# tb_target.net
KiCad netlist of a schematic drawn in EAGLE
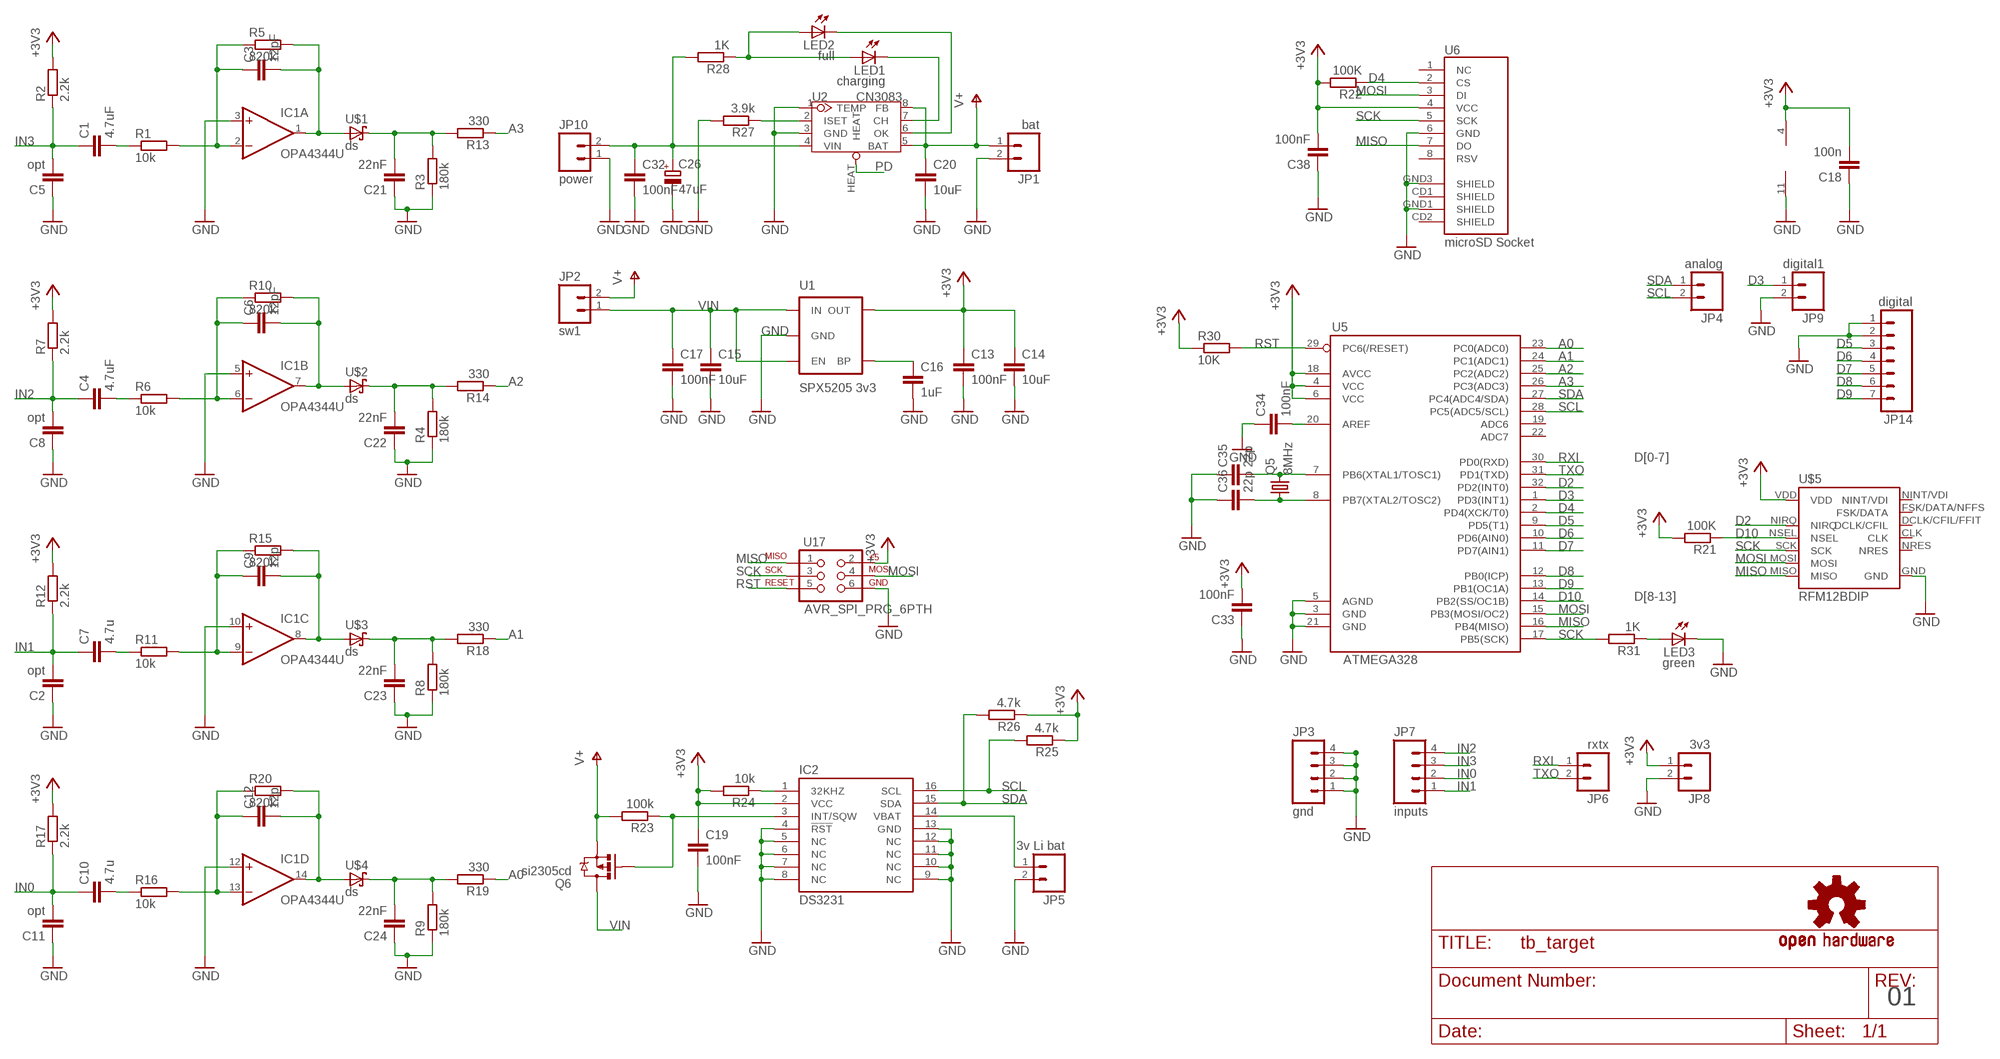
[diagram p0: schematic, sheet 1]

(export (version "E")
  (design (tool "Eeschema 10.0.6"))
  (components
    (comp (ref "C1")
      (value "4.7uF")
      (footprint "eagle-import:C0805")
      (libsource (lib "eagle-import") (part "resistor_C-EUC0805"))
    )
    (comp (ref "C2")
      (value "opt")
      (footprint "eagle-import:C0805")
      (libsource (lib "eagle-import") (part "resistor_C-EUC0805"))
    )
    (comp (ref "C3")
      (value "12pF")
      (footprint "eagle-import:C0805")
      (libsource (lib "eagle-import") (part "resistor_C-EUC0805"))
    )
    (comp (ref "C4")
      (value "4.7uF")
      (footprint "eagle-import:C0805")
      (libsource (lib "eagle-import") (part "resistor_C-EUC0805"))
    )
    (comp (ref "C5")
      (value "opt")
      (footprint "eagle-import:C0805")
      (libsource (lib "eagle-import") (part "resistor_C-EUC0805"))
    )
    (comp (ref "C6")
      (value "12pF")
      (footprint "eagle-import:C0805")
      (libsource (lib "eagle-import") (part "resistor_C-EUC0805"))
    )
    (comp (ref "C7")
      (value "4.7u")
      (footprint "eagle-import:C0805")
      (libsource (lib "eagle-import") (part "resistor_C-EUC0805"))
    )
    (comp (ref "C8")
      (value "opt")
      (footprint "eagle-import:C0805")
      (libsource (lib "eagle-import") (part "resistor_C-EUC0805"))
    )
    (comp (ref "C9")
      (value "12p")
      (footprint "eagle-import:C0805")
      (libsource (lib "eagle-import") (part "resistor_C-EUC0805"))
    )
    (comp (ref "C10")
      (value "4.7u")
      (footprint "eagle-import:C0805")
      (libsource (lib "eagle-import") (part "resistor_C-EUC0805"))
    )
    (comp (ref "C11")
      (value "opt")
      (footprint "eagle-import:C0805")
      (libsource (lib "eagle-import") (part "resistor_C-EUC0805"))
    )
    (comp (ref "C12")
      (value "12p")
      (footprint "eagle-import:C0805")
      (libsource (lib "eagle-import") (part "resistor_C-EUC0805"))
    )
    (comp (ref "C13")
      (value "100nF")
      (footprint "eagle-import:C0805")
      (libsource (lib "eagle-import") (part "C-EUC0805"))
    )
    (comp (ref "C14")
      (value "10uF")
      (footprint "eagle-import:C1206")
      (libsource (lib "eagle-import") (part "C-EUC1206"))
    )
    (comp (ref "C15")
      (value "10uF")
      (footprint "eagle-import:C1206")
      (libsource (lib "eagle-import") (part "C-EUC1206"))
    )
    (comp (ref "C16")
      (value "1uF")
      (footprint "eagle-import:C0805")
      (libsource (lib "eagle-import") (part "C-EUC0805"))
    )
    (comp (ref "C17")
      (value "100nF")
      (footprint "eagle-import:C0805")
      (libsource (lib "eagle-import") (part "C-EUC0805"))
    )
    (comp (ref "C18")
      (value "100n")
      (footprint "eagle-import:C0805")
      (libsource (lib "eagle-import") (part "resistor_C-EUC0805"))
    )
    (comp (ref "C19")
      (value "100nF")
      (footprint "eagle-import:C0805")
      (libsource (lib "eagle-import") (part "C-EUC0805"))
    )
    (comp (ref "C20")
      (value "10uF")
      (footprint "eagle-import:C1206")
      (libsource (lib "eagle-import") (part "C-EUC1206"))
    )
    (comp (ref "C21")
      (value "22nF")
      (footprint "eagle-import:C0805")
      (libsource (lib "eagle-import") (part "resistor_C-EUC0805"))
    )
    (comp (ref "C22")
      (value "22nF")
      (footprint "eagle-import:C0805")
      (libsource (lib "eagle-import") (part "resistor_C-EUC0805"))
    )
    (comp (ref "C23")
      (value "22nF")
      (footprint "eagle-import:C0805")
      (libsource (lib "eagle-import") (part "resistor_C-EUC0805"))
    )
    (comp (ref "C24")
      (value "22nF")
      (footprint "eagle-import:C0805")
      (libsource (lib "eagle-import") (part "resistor_C-EUC0805"))
    )
    (comp (ref "C26")
      (value "47uF")
      (footprint "eagle-import:CT7343")
      (libsource (lib "eagle-import") (part "CPOL-EUCT7343"))
    )
    (comp (ref "C32")
      (value "100nF")
      (footprint "eagle-import:C0805")
      (libsource (lib "eagle-import") (part "C-EUC0805"))
    )
    (comp (ref "C33")
      (value "100nF")
      (footprint "eagle-import:C0805")
      (libsource (lib "eagle-import") (part "C-EUC0805"))
    )
    (comp (ref "C34")
      (value "100nF")
      (footprint "eagle-import:C0805")
      (libsource (lib "eagle-import") (part "C-EUC0805"))
    )
    (comp (ref "C35")
      (value "22p")
      (footprint "eagle-import:C0805")
      (libsource (lib "eagle-import") (part "C-EUC0805"))
    )
    (comp (ref "C36")
      (value "22p")
      (footprint "eagle-import:C0805")
      (libsource (lib "eagle-import") (part "C-EUC0805"))
    )
    (comp (ref "C38")
      (value "100nF")
      (footprint "eagle-import:C0805")
      (libsource (lib "eagle-import") (part "C-EUC0805"))
    )
    (comp (ref "IC1")
      (value "OPA4344U")
      (footprint "eagle-import:SO14")
      (libsource (lib "eagle-import") (part "OPA4U344"))
    )
    (comp (ref "IC2")
      (value "DS3231")
      (footprint "eagle-import:SO-16")
      (libsource (lib "eagle-import") (part "DS3231"))
    )
    (comp (ref "JP1")
      (value "bat")
      (footprint "eagle-import:1X02")
      (libsource (lib "eagle-import") (part "M02PTH"))
    )
    (comp (ref "JP2")
      (value "sw1")
      (footprint "eagle-import:1X02")
      (libsource (lib "eagle-import") (part "M02PTH"))
    )
    (comp (ref "JP3")
      (value "gnd")
      (footprint "eagle-import:1X04")
      (libsource (lib "eagle-import") (part "M04PTH"))
    )
    (comp (ref "JP4")
      (value "analog")
      (footprint "eagle-import:1X02")
      (libsource (lib "eagle-import") (part "M02PTH"))
    )
    (comp (ref "JP5")
      (value "3v Li bat")
      (footprint "eagle-import:1X02")
      (libsource (lib "eagle-import") (part "M02PTH"))
    )
    (comp (ref "JP6")
      (value "rxtx")
      (footprint "eagle-import:1X02")
      (libsource (lib "eagle-import") (part "M02PTH"))
    )
    (comp (ref "JP7")
      (value "inputs")
      (footprint "eagle-import:1X04")
      (libsource (lib "eagle-import") (part "M04PTH"))
    )
    (comp (ref "JP8")
      (value "3v3")
      (footprint "eagle-import:1X02")
      (libsource (lib "eagle-import") (part "M02PTH"))
    )
    (comp (ref "JP9")
      (value "digital1")
      (footprint "eagle-import:1X02")
      (libsource (lib "eagle-import") (part "M02PTH"))
    )
    (comp (ref "JP10")
      (value "power")
      (footprint "eagle-import:1X02")
      (libsource (lib "eagle-import") (part "M02PTH"))
    )
    (comp (ref "JP14")
      (value "digital")
      (footprint "eagle-import:1X07")
      (libsource (lib "eagle-import") (part "M07"))
    )
    (comp (ref "LED1")
      (value "charging")
      (footprint "eagle-import:CHIP-LED0805")
      (libsource (lib "eagle-import") (part "LEDCHIP-LED0805"))
    )
    (comp (ref "LED2")
      (value "full")
      (footprint "eagle-import:CHIP-LED0805")
      (libsource (lib "eagle-import") (part "LEDCHIP-LED0805"))
    )
    (comp (ref "LED3")
      (value "green")
      (footprint "eagle-import:CHIP-LED0805")
      (libsource (lib "eagle-import") (part "LEDCHIP-LED0805"))
    )
    (comp (ref "Q5")
      (value "8MHz")
      (footprint "eagle-import:CRYSTAL_5X3.2")
      (libsource (lib "eagle-import") (part "CRYTAL"))
    )
    (comp (ref "Q6")
      (value "si2305cd")
      (footprint "eagle-import:SOT23-3_POWER")
      (libsource (lib "eagle-import") (part "MOSFET-PCHANNELSMD_POWER"))
    )
    (comp (ref "R1")
      (value "10k")
      (footprint "eagle-import:R0805W")
      (libsource (lib "eagle-import") (part "resistor_R-EU_R0805W"))
    )
    (comp (ref "R2")
      (value "2.2k")
      (footprint "eagle-import:R0805W")
      (libsource (lib "eagle-import") (part "resistor_R-EU_R0805W"))
    )
    (comp (ref "R3")
      (value "180k")
      (footprint "eagle-import:R0805W")
      (libsource (lib "eagle-import") (part "resistor_R-EU_R0805W"))
    )
    (comp (ref "R4")
      (value "180k")
      (footprint "eagle-import:R0805W")
      (libsource (lib "eagle-import") (part "resistor_R-EU_R0805W"))
    )
    (comp (ref "R5")
      (value "820k")
      (footprint "eagle-import:R0805W")
      (libsource (lib "eagle-import") (part "resistor_R-EU_R0805W"))
    )
    (comp (ref "R6")
      (value "10k")
      (footprint "eagle-import:R0805W")
      (libsource (lib "eagle-import") (part "resistor_R-EU_R0805W"))
    )
    (comp (ref "R7")
      (value "2.2k")
      (footprint "eagle-import:R0805W")
      (libsource (lib "eagle-import") (part "resistor_R-EU_R0805W"))
    )
    (comp (ref "R8")
      (value "180k")
      (footprint "eagle-import:R0805W")
      (libsource (lib "eagle-import") (part "resistor_R-EU_R0805W"))
    )
    (comp (ref "R9")
      (value "180k")
      (footprint "eagle-import:R0805W")
      (libsource (lib "eagle-import") (part "resistor_R-EU_R0805W"))
    )
    (comp (ref "R10")
      (value "820k")
      (footprint "eagle-import:R0805W")
      (libsource (lib "eagle-import") (part "resistor_R-EU_R0805W"))
    )
    (comp (ref "R11")
      (value "10k")
      (footprint "eagle-import:R0805W")
      (libsource (lib "eagle-import") (part "resistor_R-EU_R0805W"))
    )
    (comp (ref "R12")
      (value "2.2k")
      (footprint "eagle-import:R0805W")
      (libsource (lib "eagle-import") (part "resistor_R-EU_R0805W"))
    )
    (comp (ref "R13")
      (value "330")
      (footprint "eagle-import:R0805W")
      (libsource (lib "eagle-import") (part "resistor_R-EU_R0805W"))
    )
    (comp (ref "R14")
      (value "330")
      (footprint "eagle-import:R0805W")
      (libsource (lib "eagle-import") (part "resistor_R-EU_R0805W"))
    )
    (comp (ref "R15")
      (value "820k")
      (footprint "eagle-import:R0805W")
      (libsource (lib "eagle-import") (part "resistor_R-EU_R0805W"))
    )
    (comp (ref "R16")
      (value "10k")
      (footprint "eagle-import:R0805W")
      (libsource (lib "eagle-import") (part "resistor_R-EU_R0805W"))
    )
    (comp (ref "R17")
      (value "2.2k")
      (footprint "eagle-import:R0805W")
      (libsource (lib "eagle-import") (part "resistor_R-EU_R0805W"))
    )
    (comp (ref "R18")
      (value "330")
      (footprint "eagle-import:R0805W")
      (libsource (lib "eagle-import") (part "resistor_R-EU_R0805W"))
    )
    (comp (ref "R19")
      (value "330")
      (footprint "eagle-import:R0805W")
      (libsource (lib "eagle-import") (part "resistor_R-EU_R0805W"))
    )
    (comp (ref "R20")
      (value "820k")
      (footprint "eagle-import:R0805W")
      (libsource (lib "eagle-import") (part "resistor_R-EU_R0805W"))
    )
    (comp (ref "R21")
      (value "100K")
      (footprint "eagle-import:R0805W")
      (libsource (lib "eagle-import") (part "R-EU_R0805W"))
    )
    (comp (ref "R22")
      (value "100K")
      (footprint "eagle-import:R0805W")
      (libsource (lib "eagle-import") (part "R-EU_R0805W"))
    )
    (comp (ref "R23")
      (value "100k")
      (footprint "eagle-import:R0805W")
      (libsource (lib "eagle-import") (part "R-EU_R0805W"))
    )
    (comp (ref "R24")
      (value "10k")
      (footprint "eagle-import:R0805W")
      (libsource (lib "eagle-import") (part "R-EU_R0805W"))
    )
    (comp (ref "R25")
      (value "4.7k")
      (footprint "eagle-import:R0805W")
      (libsource (lib "eagle-import") (part "R-EU_R0805W"))
    )
    (comp (ref "R26")
      (value "4.7k")
      (footprint "eagle-import:R0805W")
      (libsource (lib "eagle-import") (part "R-EU_R0805W"))
    )
    (comp (ref "R27")
      (value "3.9k")
      (footprint "eagle-import:R0805W")
      (libsource (lib "eagle-import") (part "R-EU_R0805W"))
    )
    (comp (ref "R28")
      (value "1K")
      (footprint "eagle-import:R0805W")
      (libsource (lib "eagle-import") (part "R-EU_R0805W"))
    )
    (comp (ref "R30")
      (value "10K")
      (footprint "eagle-import:R0805W")
      (libsource (lib "eagle-import") (part "R-EU_R0805W"))
    )
    (comp (ref "R31")
      (value "1K")
      (footprint "eagle-import:R0805W")
      (libsource (lib "eagle-import") (part "R-EU_R0805W"))
    )
    (comp (ref "U$1")
      (value "ds")
      (footprint "eagle-import:SOD80")
      (libsource (lib "eagle-import") (part "DIODE-SCHOTTKYMINIMELF"))
    )
    (comp (ref "U$2")
      (value "ds")
      (footprint "eagle-import:SOD80")
      (libsource (lib "eagle-import") (part "DIODE-SCHOTTKYMINIMELF"))
    )
    (comp (ref "U$3")
      (value "ds")
      (footprint "eagle-import:SOD80")
      (libsource (lib "eagle-import") (part "DIODE-SCHOTTKYMINIMELF"))
    )
    (comp (ref "U$4")
      (value "ds")
      (footprint "eagle-import:SOD80")
      (libsource (lib "eagle-import") (part "DIODE-SCHOTTKYMINIMELF"))
    )
    (comp (ref "U$5")
      (value "RFM12BDIP")
      (footprint "eagle-import:RFM12B_DIP")
      (libsource (lib "eagle-import") (part "RFM12BDIP"))
    )
    (comp (ref "U$7")
      (value "OSHW-LOGOM")
      (footprint "eagle-import:OSHW-LOGO-M")
      (libsource (lib "eagle-import") (part "OSHW-LOGOM"))
    )
    (comp (ref "U1")
      (value "SPX5205 3v3")
      (footprint "eagle-import:SOT23-5")
      (libsource (lib "eagle-import") (part "V_REG_LDOSMD"))
    )
    (comp (ref "U2")
      (value "CN3083")
      (footprint "eagle-import:SOP8-W_-HEAT")
      (libsource (lib "eagle-import") (part "CN3083"))
    )
    (comp (ref "U5")
      (value "ATMEGA328")
      (footprint "eagle-import:TQFP32-08")
      (libsource (lib "eagle-import") (part "ATMEGA168"))
    )
    (comp (ref "U6")
      (value "microSD Socket")
      (footprint "eagle-import:MICRO-SD-SOCKET-PP")
      (libsource (lib "eagle-import") (part "USD-SOCKETNEW"))
    )
    (comp (ref "U17")
      (value "AVR_SPI_PRG_6PTH")
      (footprint "eagle-import:2X3")
      (libsource (lib "eagle-import") (part "AVR_SPI_PRG_6PTH"))
    )
  )
  (nets
    (net (code "1") (name "+3V3") (class "Default")
      (node (ref "C13") (pin "1") (pinfunction "1_1") (pintype "passive"))
      (node (ref "C14") (pin "1") (pinfunction "1_1") (pintype "passive"))
      (node (ref "C18") (pin "2") (pinfunction "2_2") (pintype "passive"))
      (node (ref "C19") (pin "1") (pinfunction "1_1") (pintype "passive"))
      (node (ref "C33") (pin "2") (pinfunction "2_2") (pintype "passive"))
      (node (ref "C38") (pin "2") (pinfunction "2_2") (pintype "passive"))
      (node (ref "IC1") (pin "4") (pinfunction "V+_4") (pintype "power_in"))
      (node (ref "IC2") (pin "2") (pinfunction "VCC_2") (pintype "power_in"))
      (node (ref "JP8") (pin "1") (pinfunction "1_1") (pintype "passive"))
      (node (ref "R12") (pin "2") (pinfunction "2_2") (pintype "passive"))
      (node (ref "R17") (pin "2") (pinfunction "2_2") (pintype "passive"))
      (node (ref "R2") (pin "2") (pinfunction "2_2") (pintype "passive"))
      (node (ref "R21") (pin "2") (pinfunction "2_2") (pintype "passive"))
      (node (ref "R22") (pin "2") (pinfunction "2_2") (pintype "passive"))
      (node (ref "R24") (pin "2") (pinfunction "2_2") (pintype "passive"))
      (node (ref "R25") (pin "1") (pinfunction "1_1") (pintype "passive"))
      (node (ref "R26") (pin "1") (pinfunction "1_1") (pintype "passive"))
      (node (ref "R30") (pin "1") (pinfunction "1_1") (pintype "passive"))
      (node (ref "R7") (pin "2") (pinfunction "2_2") (pintype "passive"))
      (node (ref "U$5") (pin "VDD") (pinfunction "VDD_VDD") (pintype "power_in"))
      (node (ref "U1") (pin "5") (pinfunction "OUT_5") (pintype "passive"))
      (node (ref "U17") (pin "2") (pinfunction "2_2") (pintype "passive"))
      (node (ref "U5") (pin "18") (pinfunction "AVCC_18") (pintype "bidirectional"))
      (node (ref "U5") (pin "4") (pinfunction "VCC_4") (pintype "bidirectional"))
      (node (ref "U5") (pin "6") (pinfunction "VCC_6") (pintype "bidirectional"))
      (node (ref "U6") (pin "4") (pinfunction "VCC_4") (pintype "bidirectional"))
    )
    (net (code "2") (name "/A0") (class "Default")
      (node (ref "R19") (pin "1") (pinfunction "1_1") (pintype "passive"))
      (node (ref "U5") (pin "23") (pinfunction "PC0(ADC0)_23") (pintype "bidirectional"))
    )
    (net (code "3") (name "/A1") (class "Default")
      (node (ref "R18") (pin "1") (pinfunction "1_1") (pintype "passive"))
      (node (ref "U5") (pin "24") (pinfunction "PC1(ADC1)_24") (pintype "bidirectional"))
    )
    (net (code "4") (name "/A2") (class "Default")
      (node (ref "R14") (pin "1") (pinfunction "1_1") (pintype "passive"))
      (node (ref "U5") (pin "25") (pinfunction "PC2(ADC2)_25") (pintype "bidirectional"))
    )
    (net (code "5") (name "/A3") (class "Default")
      (node (ref "R13") (pin "1") (pinfunction "1_1") (pintype "passive"))
      (node (ref "U5") (pin "26") (pinfunction "PC3(ADC3)_26") (pintype "bidirectional"))
    )
    (net (code "6") (name "/D2") (class "Default")
      (node (ref "U$5") (pin "NIRQ") (pinfunction "NIRQ_NIRQ") (pintype "output"))
      (node (ref "U5") (pin "32") (pinfunction "PD2(INT0)_32") (pintype "bidirectional"))
    )
    (net (code "7") (name "/D3") (class "Default")
      (node (ref "JP9") (pin "1") (pinfunction "1_1") (pintype "passive"))
      (node (ref "U5") (pin "1") (pinfunction "PD3(INT1)_1") (pintype "bidirectional"))
    )
    (net (code "8") (name "/D4") (class "Default")
      (node (ref "R22") (pin "1") (pinfunction "1_1") (pintype "passive"))
      (node (ref "U5") (pin "2") (pinfunction "PD4(XCK/T0)_2") (pintype "bidirectional"))
      (node (ref "U6") (pin "2") (pinfunction "CS_2") (pintype "bidirectional"))
    )
    (net (code "9") (name "/D5") (class "Default")
      (node (ref "JP14") (pin "3") (pinfunction "3_3") (pintype "passive"))
      (node (ref "U5") (pin "9") (pinfunction "PD5(T1)_9") (pintype "bidirectional"))
    )
    (net (code "10") (name "/D6") (class "Default")
      (node (ref "JP14") (pin "4") (pinfunction "4_4") (pintype "passive"))
      (node (ref "U5") (pin "10") (pinfunction "PD6(AIN0)_10") (pintype "bidirectional"))
    )
    (net (code "11") (name "/D7") (class "Default")
      (node (ref "JP14") (pin "5") (pinfunction "5_5") (pintype "passive"))
      (node (ref "U5") (pin "11") (pinfunction "PD7(AIN1)_11") (pintype "bidirectional"))
    )
    (net (code "12") (name "/D8") (class "Default")
      (node (ref "JP14") (pin "6") (pinfunction "6_6") (pintype "passive"))
      (node (ref "U5") (pin "12") (pinfunction "PB0(ICP)_12") (pintype "bidirectional"))
    )
    (net (code "13") (name "/D9") (class "Default")
      (node (ref "JP14") (pin "7") (pinfunction "7_7") (pintype "passive"))
      (node (ref "U5") (pin "13") (pinfunction "PB1(OC1A)_13") (pintype "bidirectional"))
    )
    (net (code "14") (name "/D10") (class "Default")
      (node (ref "R21") (pin "1") (pinfunction "1_1") (pintype "passive"))
      (node (ref "U$5") (pin "NSEL") (pinfunction "NSEL_NSEL") (pintype "input"))
      (node (ref "U5") (pin "14") (pinfunction "PB2(SS/OC1B)_14") (pintype "bidirectional"))
    )
    (net (code "15") (name "/IN0") (class "Default")
      (node (ref "C10") (pin "1") (pinfunction "1_1") (pintype "passive"))
      (node (ref "C11") (pin "2") (pinfunction "2_2") (pintype "passive"))
      (node (ref "JP7") (pin "2") (pinfunction "2_2") (pintype "passive"))
      (node (ref "R17") (pin "1") (pinfunction "1_1") (pintype "passive"))
    )
    (net (code "16") (name "/IN1") (class "Default")
      (node (ref "C2") (pin "2") (pinfunction "2_2") (pintype "passive"))
      (node (ref "C7") (pin "1") (pinfunction "1_1") (pintype "passive"))
      (node (ref "JP7") (pin "1") (pinfunction "1_1") (pintype "passive"))
      (node (ref "R12") (pin "1") (pinfunction "1_1") (pintype "passive"))
    )
    (net (code "17") (name "/IN2") (class "Default")
      (node (ref "C4") (pin "1") (pinfunction "1_1") (pintype "passive"))
      (node (ref "C8") (pin "2") (pinfunction "2_2") (pintype "passive"))
      (node (ref "JP7") (pin "4") (pinfunction "4_4") (pintype "passive"))
      (node (ref "R7") (pin "1") (pinfunction "1_1") (pintype "passive"))
    )
    (net (code "18") (name "/IN3") (class "Default")
      (node (ref "C1") (pin "1") (pinfunction "1_1") (pintype "passive"))
      (node (ref "C5") (pin "2") (pinfunction "2_2") (pintype "passive"))
      (node (ref "JP7") (pin "3") (pinfunction "3_3") (pintype "passive"))
      (node (ref "R2") (pin "1") (pinfunction "1_1") (pintype "passive"))
    )
    (net (code "19") (name "/MISO") (class "Default")
      (node (ref "U$5") (pin "MISO") (pinfunction "MISO_MISO") (pintype "output"))
      (node (ref "U17") (pin "1") (pinfunction "1_1") (pintype "passive"))
      (node (ref "U5") (pin "16") (pinfunction "PB4(MISO)_16") (pintype "bidirectional"))
      (node (ref "U6") (pin "7") (pinfunction "DO_7") (pintype "bidirectional"))
    )
    (net (code "20") (name "/MOSI") (class "Default")
      (node (ref "U$5") (pin "MOSI") (pinfunction "MOSI_MOSI") (pintype "input"))
      (node (ref "U17") (pin "4") (pinfunction "4_4") (pintype "passive"))
      (node (ref "U5") (pin "15") (pinfunction "PB3(MOSI/OC2)_15") (pintype "bidirectional"))
      (node (ref "U6") (pin "3") (pinfunction "DI_3") (pintype "bidirectional"))
    )
    (net (code "21") (name "/PD") (class "Default")
      (node (ref "U2") (pin "HEAT") (pinfunction "HEAT_HEAT") (pintype "bidirectional"))
    )
    (net (code "22") (name "/RST") (class "Default")
      (node (ref "R30") (pin "2") (pinfunction "2_2") (pintype "passive"))
      (node (ref "U17") (pin "5") (pinfunction "5_5") (pintype "passive"))
      (node (ref "U5") (pin "29") (pinfunction "PC6(/RESET)_29") (pintype "bidirectional"))
    )
    (net (code "23") (name "/RXI") (class "Default")
      (node (ref "JP6") (pin "1") (pinfunction "1_1") (pintype "passive"))
      (node (ref "U5") (pin "30") (pinfunction "PD0(RXD)_30") (pintype "bidirectional"))
    )
    (net (code "24") (name "/SCK") (class "Default")
      (node (ref "R31") (pin "2") (pinfunction "2_2") (pintype "passive"))
      (node (ref "U$5") (pin "SCK") (pinfunction "SCK_SCK") (pintype "input"))
      (node (ref "U17") (pin "3") (pinfunction "3_3") (pintype "passive"))
      (node (ref "U5") (pin "17") (pinfunction "PB5(SCK)_17") (pintype "bidirectional"))
      (node (ref "U6") (pin "5") (pinfunction "SCK_5") (pintype "bidirectional"))
    )
    (net (code "25") (name "/SCL") (class "Default")
      (node (ref "IC2") (pin "16") (pinfunction "SCL_16") (pintype "bidirectional"))
      (node (ref "JP4") (pin "2") (pinfunction "2_2") (pintype "passive"))
      (node (ref "R25") (pin "2") (pinfunction "2_2") (pintype "passive"))
      (node (ref "U5") (pin "28") (pinfunction "PC5(ADC5/SCL)_28") (pintype "bidirectional"))
    )
    (net (code "26") (name "/SDA") (class "Default")
      (node (ref "IC2") (pin "15") (pinfunction "SDA_15") (pintype "bidirectional"))
      (node (ref "JP4") (pin "1") (pinfunction "1_1") (pintype "passive"))
      (node (ref "R26") (pin "2") (pinfunction "2_2") (pintype "passive"))
      (node (ref "U5") (pin "27") (pinfunction "PC4(ADC4/SDA)_27") (pintype "bidirectional"))
    )
    (net (code "27") (name "/TXO") (class "Default")
      (node (ref "JP6") (pin "2") (pinfunction "2_2") (pintype "passive"))
      (node (ref "U5") (pin "31") (pinfunction "PD1(TXD)_31") (pintype "bidirectional"))
    )
    (net (code "28") (name "/VIN") (class "Default")
      (node (ref "C15") (pin "1") (pinfunction "1_1") (pintype "passive"))
      (node (ref "C17") (pin "1") (pinfunction "1_1") (pintype "passive"))
      (node (ref "JP2") (pin "1") (pinfunction "1_1") (pintype "passive"))
      (node (ref "Q6") (pin "3") (pinfunction "D_3") (pintype "passive"))
      (node (ref "U1") (pin "1") (pinfunction "IN_1") (pintype "input"))
      (node (ref "U1") (pin "3") (pinfunction "EN_3") (pintype "input"))
    )
    (net (code "29") (name "GND") (class "Default")
      (node (ref "C11") (pin "1") (pinfunction "1_1") (pintype "passive"))
      (node (ref "C13") (pin "2") (pinfunction "2_2") (pintype "passive"))
      (node (ref "C14") (pin "2") (pinfunction "2_2") (pintype "passive"))
      (node (ref "C15") (pin "2") (pinfunction "2_2") (pintype "passive"))
      (node (ref "C16") (pin "2") (pinfunction "2_2") (pintype "passive"))
      (node (ref "C17") (pin "2") (pinfunction "2_2") (pintype "passive"))
      (node (ref "C18") (pin "1") (pinfunction "1_1") (pintype "passive"))
      (node (ref "C19") (pin "2") (pinfunction "2_2") (pintype "passive"))
      (node (ref "C2") (pin "1") (pinfunction "1_1") (pintype "passive"))
      (node (ref "C20") (pin "2") (pinfunction "2_2") (pintype "passive"))
      (node (ref "C21") (pin "1") (pinfunction "1_1") (pintype "passive"))
      (node (ref "C22") (pin "1") (pinfunction "1_1") (pintype "passive"))
      (node (ref "C23") (pin "1") (pinfunction "1_1") (pintype "passive"))
      (node (ref "C24") (pin "1") (pinfunction "1_1") (pintype "passive"))
      (node (ref "C26") (pin "-") (pinfunction "-_-") (pintype "passive"))
      (node (ref "C32") (pin "2") (pinfunction "2_2") (pintype "passive"))
      (node (ref "C33") (pin "1") (pinfunction "1_1") (pintype "passive"))
      (node (ref "C34") (pin "1") (pinfunction "1_1") (pintype "passive"))
      (node (ref "C35") (pin "1") (pinfunction "1_1") (pintype "passive"))
      (node (ref "C36") (pin "1") (pinfunction "1_1") (pintype "passive"))
      (node (ref "C38") (pin "1") (pinfunction "1_1") (pintype "passive"))
      (node (ref "C5") (pin "1") (pinfunction "1_1") (pintype "passive"))
      (node (ref "C8") (pin "1") (pinfunction "1_1") (pintype "passive"))
      (node (ref "IC1") (pin "10") (pinfunction "+IN_10") (pintype "input"))
      (node (ref "IC1") (pin "11") (pinfunction "V-_11") (pintype "power_in"))
      (node (ref "IC1") (pin "12") (pinfunction "+IN_12") (pintype "input"))
      (node (ref "IC1") (pin "3") (pinfunction "+IN_3") (pintype "input"))
      (node (ref "IC1") (pin "5") (pinfunction "+IN_5") (pintype "input"))
      (node (ref "IC2") (pin "10") (pinfunction "NC_10") (pintype "bidirectional"))
      (node (ref "IC2") (pin "11") (pinfunction "NC_11") (pintype "bidirectional"))
      (node (ref "IC2") (pin "12") (pinfunction "NC_12") (pintype "bidirectional"))
      (node (ref "IC2") (pin "13") (pinfunction "GND_13") (pintype "power_in"))
      (node (ref "IC2") (pin "4") (pinfunction "~{RST}_4") (pintype "bidirectional"))
      (node (ref "IC2") (pin "5") (pinfunction "NC_5") (pintype "bidirectional"))
      (node (ref "IC2") (pin "6") (pinfunction "NC_6") (pintype "bidirectional"))
      (node (ref "IC2") (pin "7") (pinfunction "NC_7") (pintype "bidirectional"))
      (node (ref "IC2") (pin "8") (pinfunction "NC_8") (pintype "bidirectional"))
      (node (ref "IC2") (pin "9") (pinfunction "NC_9") (pintype "bidirectional"))
      (node (ref "JP1") (pin "2") (pinfunction "2_2") (pintype "passive"))
      (node (ref "JP10") (pin "1") (pinfunction "1_1") (pintype "passive"))
      (node (ref "JP14") (pin "1") (pinfunction "1_1") (pintype "passive"))
      (node (ref "JP14") (pin "2") (pinfunction "2_2") (pintype "passive"))
      (node (ref "JP3") (pin "1") (pinfunction "1_1") (pintype "passive"))
      (node (ref "JP3") (pin "2") (pinfunction "2_2") (pintype "passive"))
      (node (ref "JP3") (pin "3") (pinfunction "3_3") (pintype "passive"))
      (node (ref "JP3") (pin "4") (pinfunction "4_4") (pintype "passive"))
      (node (ref "JP5") (pin "2") (pinfunction "2_2") (pintype "passive"))
      (node (ref "JP8") (pin "2") (pinfunction "2_2") (pintype "passive"))
      (node (ref "JP9") (pin "2") (pinfunction "2_2") (pintype "passive"))
      (node (ref "LED3") (pin "C") (pinfunction "C_C") (pintype "passive"))
      (node (ref "R27") (pin "2") (pinfunction "2_2") (pintype "passive"))
      (node (ref "R3") (pin "1") (pinfunction "1_1") (pintype "passive"))
      (node (ref "R4") (pin "1") (pinfunction "1_1") (pintype "passive"))
      (node (ref "R8") (pin "1") (pinfunction "1_1") (pintype "passive"))
      (node (ref "R9") (pin "1") (pinfunction "1_1") (pintype "passive"))
      (node (ref "U$5") (pin "GND") (pinfunction "GND_GND") (pintype "power_in"))
      (node (ref "U1") (pin "2") (pinfunction "GND_2") (pintype "input"))
      (node (ref "U17") (pin "6") (pinfunction "6_6") (pintype "passive"))
      (node (ref "U2") (pin "1") (pinfunction "TEMP_1") (pintype "bidirectional"))
      (node (ref "U2") (pin "3") (pinfunction "GND_3") (pintype "bidirectional"))
      (node (ref "U5") (pin "21") (pinfunction "GND_21") (pintype "bidirectional"))
      (node (ref "U5") (pin "3") (pinfunction "GND_3") (pintype "bidirectional"))
      (node (ref "U5") (pin "5") (pinfunction "AGND_5") (pintype "bidirectional"))
      (node (ref "U6") (pin "6") (pinfunction "GND_6") (pintype "bidirectional"))
      (node (ref "U6") (pin "GND1") (pinfunction "SHIELD_GND1") (pintype "bidirectional"))
      (node (ref "U6") (pin "GND3") (pinfunction "SHIELD_GND3") (pintype "bidirectional"))
    )
    (net (code "30") (name "Net-(C1-Pad2)") (class "Default")
      (node (ref "C1") (pin "2") (pinfunction "2_2") (pintype "passive"))
      (node (ref "R1") (pin "1") (pinfunction "1_1") (pintype "passive"))
    )
    (net (code "31") (name "Net-(C4-Pad2)") (class "Default")
      (node (ref "C4") (pin "2") (pinfunction "2_2") (pintype "passive"))
      (node (ref "R6") (pin "1") (pinfunction "1_1") (pintype "passive"))
    )
    (net (code "32") (name "Net-(C7-Pad2)") (class "Default")
      (node (ref "C7") (pin "2") (pinfunction "2_2") (pintype "passive"))
      (node (ref "R11") (pin "1") (pinfunction "1_1") (pintype "passive"))
    )
    (net (code "33") (name "Net-(C10-Pad2)") (class "Default")
      (node (ref "C10") (pin "2") (pinfunction "2_2") (pintype "passive"))
      (node (ref "R16") (pin "1") (pinfunction "1_1") (pintype "passive"))
    )
    (net (code "34") (name "Net-(C21-Pad2)") (class "Default")
      (node (ref "C21") (pin "2") (pinfunction "2_2") (pintype "passive"))
      (node (ref "R13") (pin "2") (pinfunction "2_2") (pintype "passive"))
      (node (ref "R3") (pin "2") (pinfunction "2_2") (pintype "passive"))
      (node (ref "U$1") (pin "C") (pinfunction "C_C") (pintype "passive"))
    )
    (net (code "35") (name "Net-(C22-Pad2)") (class "Default")
      (node (ref "C22") (pin "2") (pinfunction "2_2") (pintype "passive"))
      (node (ref "R14") (pin "2") (pinfunction "2_2") (pintype "passive"))
      (node (ref "R4") (pin "2") (pinfunction "2_2") (pintype "passive"))
      (node (ref "U$2") (pin "C") (pinfunction "C_C") (pintype "passive"))
    )
    (net (code "36") (name "Net-(C23-Pad2)") (class "Default")
      (node (ref "C23") (pin "2") (pinfunction "2_2") (pintype "passive"))
      (node (ref "R18") (pin "2") (pinfunction "2_2") (pintype "passive"))
      (node (ref "R8") (pin "2") (pinfunction "2_2") (pintype "passive"))
      (node (ref "U$3") (pin "C") (pinfunction "C_C") (pintype "passive"))
    )
    (net (code "37") (name "Net-(C24-Pad2)") (class "Default")
      (node (ref "C24") (pin "2") (pinfunction "2_2") (pintype "passive"))
      (node (ref "R19") (pin "2") (pinfunction "2_2") (pintype "passive"))
      (node (ref "R9") (pin "2") (pinfunction "2_2") (pintype "passive"))
      (node (ref "U$4") (pin "C") (pinfunction "C_C") (pintype "passive"))
    )
    (net (code "38") (name "Net-(IC1A--IN)") (class "Default")
      (node (ref "C3") (pin "1") (pinfunction "1_1") (pintype "passive"))
      (node (ref "IC1") (pin "2") (pinfunction "-IN_2") (pintype "input"))
      (node (ref "R1") (pin "2") (pinfunction "2_2") (pintype "passive"))
      (node (ref "R5") (pin "1") (pinfunction "1_1") (pintype "passive"))
    )
    (net (code "39") (name "Net-(IC1A-OUT)") (class "Default")
      (node (ref "C3") (pin "2") (pinfunction "2_2") (pintype "passive"))
      (node (ref "IC1") (pin "1") (pinfunction "OUT_1") (pintype "output"))
      (node (ref "R5") (pin "2") (pinfunction "2_2") (pintype "passive"))
      (node (ref "U$1") (pin "A") (pinfunction "A_A") (pintype "passive"))
    )
    (net (code "40") (name "Net-(IC1B--IN)") (class "Default")
      (node (ref "C6") (pin "1") (pinfunction "1_1") (pintype "passive"))
      (node (ref "IC1") (pin "6") (pinfunction "-IN_6") (pintype "input"))
      (node (ref "R10") (pin "1") (pinfunction "1_1") (pintype "passive"))
      (node (ref "R6") (pin "2") (pinfunction "2_2") (pintype "passive"))
    )
    (net (code "41") (name "Net-(IC1B-OUT)") (class "Default")
      (node (ref "C6") (pin "2") (pinfunction "2_2") (pintype "passive"))
      (node (ref "IC1") (pin "7") (pinfunction "OUT_7") (pintype "output"))
      (node (ref "R10") (pin "2") (pinfunction "2_2") (pintype "passive"))
      (node (ref "U$2") (pin "A") (pinfunction "A_A") (pintype "passive"))
    )
    (net (code "42") (name "Net-(IC1C--IN)") (class "Default")
      (node (ref "C9") (pin "1") (pinfunction "1_1") (pintype "passive"))
      (node (ref "IC1") (pin "9") (pinfunction "-IN_9") (pintype "input"))
      (node (ref "R11") (pin "2") (pinfunction "2_2") (pintype "passive"))
      (node (ref "R15") (pin "1") (pinfunction "1_1") (pintype "passive"))
    )
    (net (code "43") (name "Net-(IC1C-OUT)") (class "Default")
      (node (ref "C9") (pin "2") (pinfunction "2_2") (pintype "passive"))
      (node (ref "IC1") (pin "8") (pinfunction "OUT_8") (pintype "output"))
      (node (ref "R15") (pin "2") (pinfunction "2_2") (pintype "passive"))
      (node (ref "U$3") (pin "A") (pinfunction "A_A") (pintype "passive"))
    )
    (net (code "44") (name "Net-(IC1D--IN)") (class "Default")
      (node (ref "C12") (pin "1") (pinfunction "1_1") (pintype "passive"))
      (node (ref "IC1") (pin "13") (pinfunction "-IN_13") (pintype "input"))
      (node (ref "R16") (pin "2") (pinfunction "2_2") (pintype "passive"))
      (node (ref "R20") (pin "1") (pinfunction "1_1") (pintype "passive"))
    )
    (net (code "45") (name "Net-(IC1D-OUT)") (class "Default")
      (node (ref "C12") (pin "2") (pinfunction "2_2") (pintype "passive"))
      (node (ref "IC1") (pin "14") (pinfunction "OUT_14") (pintype "output"))
      (node (ref "R20") (pin "2") (pinfunction "2_2") (pintype "passive"))
      (node (ref "U$4") (pin "A") (pinfunction "A_A") (pintype "passive"))
    )
    (net (code "46") (name "Net-(IC2-32KHZ)") (class "Default")
      (node (ref "IC2") (pin "1") (pinfunction "32KHZ_1") (pintype "bidirectional"))
      (node (ref "R24") (pin "1") (pinfunction "1_1") (pintype "passive"))
    )
    (net (code "47") (name "Net-(IC2-INT{slash}SQW)") (class "Default")
      (node (ref "IC2") (pin "3") (pinfunction "INT/SQW_3") (pintype "bidirectional"))
      (node (ref "Q6") (pin "1") (pinfunction "G_1") (pintype "passive"))
      (node (ref "R23") (pin "1") (pinfunction "1_1") (pintype "passive"))
    )
    (net (code "48") (name "Net-(IC2-VBAT)") (class "Default")
      (node (ref "IC2") (pin "14") (pinfunction "VBAT_14") (pintype "bidirectional"))
      (node (ref "JP5") (pin "1") (pinfunction "1_1") (pintype "passive"))
    )
    (net (code "49") (name "Net-(LED1-PadA)") (class "Default")
      (node (ref "LED1") (pin "A") (pinfunction "A_A") (pintype "passive"))
      (node (ref "LED2") (pin "A") (pinfunction "A_A") (pintype "passive"))
      (node (ref "R28") (pin "1") (pinfunction "1_1") (pintype "passive"))
    )
    (net (code "50") (name "Net-(LED3-PadA)") (class "Default")
      (node (ref "LED3") (pin "A") (pinfunction "A_A") (pintype "passive"))
      (node (ref "R31") (pin "1") (pinfunction "1_1") (pintype "passive"))
    )
    (net (code "51") (name "Net-(Q5-1)") (class "Default")
      (node (ref "C36") (pin "2") (pinfunction "2_2") (pintype "passive"))
      (node (ref "Q5") (pin "P$1") (pinfunction "1_P$1") (pintype "passive"))
      (node (ref "U5") (pin "8") (pinfunction "PB7(XTAL2/TOSC2)_8") (pintype "bidirectional"))
    )
    (net (code "52") (name "Net-(Q5-2)") (class "Default")
      (node (ref "C35") (pin "2") (pinfunction "2_2") (pintype "passive"))
      (node (ref "Q5") (pin "P$2") (pinfunction "2_P$2") (pintype "passive"))
      (node (ref "U5") (pin "7") (pinfunction "PB6(XTAL1/TOSC1)_7") (pintype "bidirectional"))
    )
    (net (code "53") (name "Net-(U1-BP)") (class "Default")
      (node (ref "C16") (pin "1") (pinfunction "1_1") (pintype "passive"))
      (node (ref "U1") (pin "4") (pinfunction "BP_4") (pintype "input"))
    )
    (net (code "54") (name "Net-(U2-CH)") (class "Default")
      (node (ref "LED1") (pin "C") (pinfunction "C_C") (pintype "passive"))
      (node (ref "U2") (pin "7") (pinfunction "CH_7") (pintype "bidirectional"))
    )
    (net (code "55") (name "Net-(U2-ISET)") (class "Default")
      (node (ref "R27") (pin "1") (pinfunction "1_1") (pintype "passive"))
      (node (ref "U2") (pin "2") (pinfunction "ISET_2") (pintype "bidirectional"))
    )
    (net (code "56") (name "Net-(U2-OK)") (class "Default")
      (node (ref "LED2") (pin "C") (pinfunction "C_C") (pintype "passive"))
      (node (ref "U2") (pin "6") (pinfunction "OK_6") (pintype "bidirectional"))
    )
    (net (code "57") (name "Net-(U2-VIN)") (class "Default")
      (node (ref "C26") (pin "+") (pinfunction "+_+") (pintype "passive"))
      (node (ref "C32") (pin "1") (pinfunction "1_1") (pintype "passive"))
      (node (ref "JP10") (pin "2") (pinfunction "2_2") (pintype "passive"))
      (node (ref "R28") (pin "2") (pinfunction "2_2") (pintype "passive"))
      (node (ref "U2") (pin "4") (pinfunction "VIN_4") (pintype "bidirectional"))
    )
    (net (code "58") (name "Net-(U5-AREF)") (class "Default")
      (node (ref "C34") (pin "2") (pinfunction "2_2") (pintype "passive"))
      (node (ref "U5") (pin "20") (pinfunction "AREF_20") (pintype "bidirectional"))
    )
    (net (code "59") (name "V+") (class "Default")
      (node (ref "C20") (pin "1") (pinfunction "1_1") (pintype "passive"))
      (node (ref "JP1") (pin "1") (pinfunction "1_1") (pintype "passive"))
      (node (ref "JP2") (pin "2") (pinfunction "2_2") (pintype "passive"))
      (node (ref "Q6") (pin "2") (pinfunction "S_2") (pintype "passive"))
      (node (ref "R23") (pin "2") (pinfunction "2_2") (pintype "passive"))
      (node (ref "U2") (pin "5") (pinfunction "BAT_5") (pintype "bidirectional"))
      (node (ref "U2") (pin "8") (pinfunction "FB_8") (pintype "bidirectional"))
    )
    (net (code "60") (name "unconnected-(U$5-DCLK{slash}CFIL-PadDCLK{slash}CFIL{slash}FFIT)") (class "Default")
      (node (ref "U$5") (pin "DCLK/CFIL/FFIT") (pinfunction "DCLK/CFIL_DCLK/CFIL/FFIT") (pintype "bidirectional"))
    )
    (net (code "61") (name "unconnected-(U$5-FSK{slash}DATA-PadFSK{slash}DATA{slash}NFFS)") (class "Default")
      (node (ref "U$5") (pin "FSK/DATA/NFFS") (pinfunction "FSK/DATA_FSK/DATA/NFFS") (pintype "bidirectional"))
    )
    (net (code "62") (name "unconnected-(U$5-PadCLK)") (class "Default")
      (node (ref "U$5") (pin "CLK") (pinfunction "CLK_CLK") (pintype "output"))
    )
    (net (code "63") (name "unconnected-(U$5-PadNINT{slash}VDI)") (class "Default")
      (node (ref "U$5") (pin "NINT/VDI") (pinfunction "NINT/VDI_NINT/VDI") (pintype "bidirectional"))
    )
    (net (code "64") (name "unconnected-(U$5-PadNRES)") (class "Default")
      (node (ref "U$5") (pin "NRES") (pinfunction "NRES_NRES") (pintype "bidirectional"))
    )
    (net (code "65") (name "unconnected-(U5-ADC6-Pad19)") (class "Default")
      (node (ref "U5") (pin "19") (pinfunction "ADC6_19") (pintype "bidirectional"))
    )
    (net (code "66") (name "unconnected-(U5-ADC7-Pad22)") (class "Default")
      (node (ref "U5") (pin "22") (pinfunction "ADC7_22") (pintype "bidirectional"))
    )
    (net (code "67") (name "unconnected-(U6-NC-Pad1)") (class "Default")
      (node (ref "U6") (pin "1") (pinfunction "NC_1") (pintype "bidirectional"))
    )
    (net (code "68") (name "unconnected-(U6-RSV-Pad8)") (class "Default")
      (node (ref "U6") (pin "8") (pinfunction "RSV_8") (pintype "bidirectional"))
    )
    (net (code "69") (name "unconnected-(U6-SHIELD-PadCD1)") (class "Default")
      (node (ref "U6") (pin "CD1") (pinfunction "SHIELD_CD1") (pintype "bidirectional"))
    )
    (net (code "70") (name "unconnected-(U6-SHIELD-PadCD2)") (class "Default")
      (node (ref "U6") (pin "CD2") (pinfunction "SHIELD_CD2") (pintype "bidirectional"))
    )
  )
)
